# Smart_shoe_Sensor.net
KiCad netlist of a schematic drawn in Altium Designer
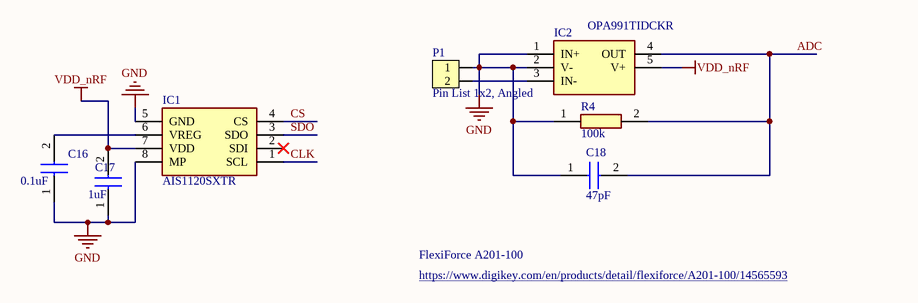
[diagram p0: Smart shoe_Sensor.SchDoc]

(export (version "E")
  (design (tool "Eeschema 10.0.6"))
  (components
    (comp (ref "C16")
      (value "0.1uF")
      (footprint "CAPC0603X03L_C")
      (description "Capacitor")
      (fields
        (field (name "MANUFACTURER_PART_NUMBER") "C0603X7S1A104K030BC")
        (field (name "MOUSER PART NUMBER") "810-C0603X7S1A104K")
      )
      (libsource (lib "*") (part "C0603X7S1A104K030BC"))
    )
    (comp (ref "C17")
      (value "1uF")
      (footprint "SamacSys:CAPC0603X33N")
      (description "Capacitor")
      (fields
        (field (name "MANUFACTURER_PART_NUMBER") "GRM033R61A105ME15E")
        (field (name "MOUSER PART NUMBER") "81-GRM033R61A105ME5E")
      )
      (libsource (lib "*") (part "GRM033R61A105ME15E"))
    )
    (comp (ref "C18")
      (value "47pF")
      (footprint "SamacSys:CAPC1005X56N")
      (description "Capacitor")
      (fields (field (name "MANUFACTURER_PART_NUMBER") "0402ZA470JAT2A"))
      (libsource (lib "*") (part "0402ZA470JAT2A"))
    )
    (comp (ref "IC1")
      (value "AIS1120SXTR")
      (footprint "SamacSys:SOIC127P600X175-8N")
      (description "Integrated Circuit")
      (fields (field (name "MOUSER PART NUMBER") "511-AIS1120SXTR"))
      (libsource (lib "*") (part "AIS1120SXTR"))
    )
    (comp (ref "IC2")
      (value "OPA991TIDCKR")
      (footprint "SamacSys:SOT65P210X110-5N")
      (description "Integrated Circuit")
      (fields (field (name "MOUSER PART NUMBER") "595-OPA991TIDCKR"))
      (libsource (lib "*") (part "OPA991TIDCKR"))
    )
    (comp (ref "P1")
      (value "Pin List 1x2, Angled")
      (footprint "LIST_ANG_1x2-SMD-2.54MM")
      (description "Pin List 1x2, 2.54mm (100mil), Right Angled, SMD")
      (fields
        (field (name "PART NUMBER") "Pin List Ang 1x2 SMD, 2.54mm")
        (field (name "MANUFACTURER") "W-CON")
        (field (name "PUBLISHER") "Nordic Semiconductor")
      )
      (libsource (lib "pca10040") (part "LIST-1x2_ANG"))
    )
    (comp (ref "R4")
      (value "100k")
      (footprint "SamacSys:RESC0402X15N")
      (description "Resistor")
      (fields
        (field (name "MANUFACTURER_PART_NUMBER") "CRCW0100100KFREL")
        (field (name "MOUSER PART NUMBER") "71-CRCW0100100KFREL")
      )
      (libsource (lib "*") (part "CRCW0100100KFREL"))
    )
  )
  (nets
    (net (code "1") (name "/ADC") (class "Default")
      (node (ref "C18") (pin "2") (pinfunction "2_2") (pintype "passive"))
      (node (ref "IC2") (pin "4") (pinfunction "OUT_4") (pintype "passive"))
      (node (ref "R4") (pin "2") (pinfunction "2_2") (pintype "passive"))
    )
    (net (code "2") (name "/CLK") (class "Default")
      (node (ref "IC1") (pin "1") (pinfunction "SCL_1") (pintype "passive"))
    )
    (net (code "3") (name "/CS") (class "Default")
      (node (ref "IC1") (pin "4") (pinfunction "CS_4") (pintype "passive"))
    )
    (net (code "4") (name "/SDO") (class "Default")
      (node (ref "IC1") (pin "3") (pinfunction "SDO_3") (pintype "passive"))
    )
    (net (code "5") (name "GND") (class "Default")
      (node (ref "C16") (pin "1") (pinfunction "1_1") (pintype "passive"))
      (node (ref "C17") (pin "1") (pinfunction "1_1") (pintype "passive"))
      (node (ref "C18") (pin "1") (pinfunction "1_1") (pintype "passive"))
      (node (ref "IC1") (pin "5") (pinfunction "GND_5") (pintype "passive"))
      (node (ref "IC1") (pin "8") (pinfunction "MP_8") (pintype "passive"))
      (node (ref "IC2") (pin "1") (pinfunction "IN+_1") (pintype "passive"))
      (node (ref "IC2") (pin "2") (pinfunction "V-_2") (pintype "passive"))
      (node (ref "P1") (pin "1") (pinfunction "1_1") (pintype "passive"))
      (node (ref "R4") (pin "1") (pinfunction "1_1") (pintype "passive"))
    )
    (net (code "6") (name "Net-(IC1-VREG)") (class "Default")
      (node (ref "C16") (pin "2") (pinfunction "2_2") (pintype "passive"))
      (node (ref "IC1") (pin "6") (pinfunction "VREG_6") (pintype "passive"))
    )
    (net (code "7") (name "Net-(IC2-IN-)") (class "Default")
      (node (ref "IC2") (pin "3") (pinfunction "IN-_3") (pintype "passive"))
      (node (ref "P1") (pin "2") (pinfunction "2_2") (pintype "passive"))
    )
    (net (code "8") (name "VDD_nRF") (class "Default")
      (node (ref "C17") (pin "2") (pinfunction "2_2") (pintype "passive"))
      (node (ref "IC1") (pin "7") (pinfunction "VDD_7") (pintype "passive"))
      (node (ref "IC2") (pin "5") (pinfunction "V+_5") (pintype "passive"))
    )
    (net (code "9") (name "unconnected-(IC1-SDI-Pad2)") (class "Default")
      (node (ref "IC1") (pin "2") (pinfunction "SDI_2") (pintype "passive+no_connect"))
    )
  )
)
